# Sheet1.net
KiCad netlist of a schematic drawn in Altium Designer
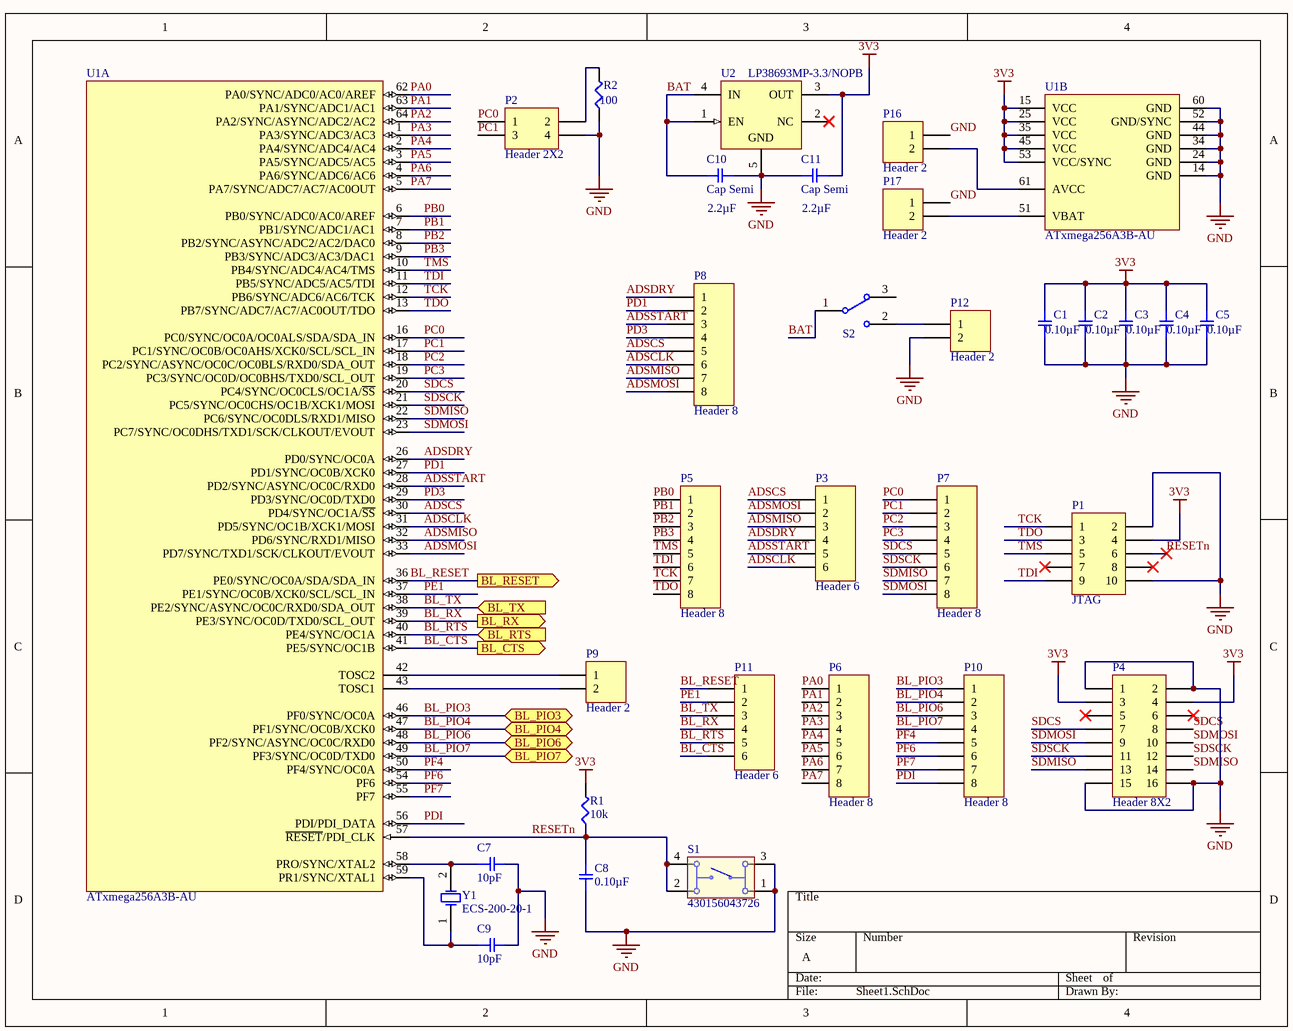
[diagram p0: Sheet1.SchDoc]

(export (version "E")
  (design (tool "Eeschema 10.0.6"))
  (components
    (comp (ref "C1")
      (value "0.10µF")
      (footprint "SMD-0805C")
      (description "CAP CER 0.1UF 50V X7R 0805")
      (fields
        (field (name "DIGI-KEY PART NUMBER") "490-11955-1-ND")
        (field (name "PART NUMBER") "GCD21BR71H104KA01L")
      )
      (libsource (lib "capacitor_murata_0805") (part "GCD21BR71H104KA01L"))
    )
    (comp (ref "C2")
      (value "0.10µF")
      (footprint "SMD-0805C")
      (description "CAP CER 0.1UF 50V X7R 0805")
      (fields
        (field (name "DIGI-KEY PART NUMBER") "490-11955-1-ND")
        (field (name "PART NUMBER") "GCD21BR71H104KA01L")
      )
      (libsource (lib "capacitor_murata_0805") (part "GCD21BR71H104KA01L"))
    )
    (comp (ref "C3")
      (value "0.10µF")
      (footprint "SMD-0805C")
      (description "CAP CER 0.1UF 50V X7R 0805")
      (fields
        (field (name "DIGI-KEY PART NUMBER") "490-11955-1-ND")
        (field (name "PART NUMBER") "GCD21BR71H104KA01L")
      )
      (libsource (lib "capacitor_murata_0805") (part "GCD21BR71H104KA01L"))
    )
    (comp (ref "C4")
      (value "0.10µF")
      (footprint "SMD-0805C")
      (description "CAP CER 0.1UF 50V X7R 0805")
      (fields
        (field (name "DIGI-KEY PART NUMBER") "490-11955-1-ND")
        (field (name "PART NUMBER") "GCD21BR71H104KA01L")
      )
      (libsource (lib "capacitor_murata_0805") (part "GCD21BR71H104KA01L"))
    )
    (comp (ref "C5")
      (value "0.10µF")
      (footprint "SMD-0805C")
      (description "CAP CER 0.1UF 50V X7R 0805")
      (fields
        (field (name "DIGI-KEY PART NUMBER") "490-11955-1-ND")
        (field (name "PART NUMBER") "GCD21BR71H104KA01L")
      )
      (libsource (lib "capacitor_murata_0805") (part "GCD21BR71H104KA01L"))
    )
    (comp (ref "C7")
      (value "10pF")
      (footprint "SMD-1206C")
      (description "CAP CER 10PF 630V U2J 1206")
      (fields
        (field (name "DIGI-KEY PART NUMBER") "490-6495-1-ND")
        (field (name "PART NUMBER") "GRM31A7U2J100JW31D")
      )
      (libsource (lib "capacitor_murata_1206") (part "GRM31A7U2J100JW31D"))
    )
    (comp (ref "C8")
      (value "0.10µF")
      (footprint "SMD-0805C")
      (description "CAP CER 0.1UF 50V X7R 0805")
      (fields
        (field (name "DIGI-KEY PART NUMBER") "490-11955-1-ND")
        (field (name "PART NUMBER") "GCD21BR71H104KA01L")
      )
      (libsource (lib "capacitor_murata_0805") (part "GCD21BR71H104KA01L"))
    )
    (comp (ref "C9")
      (value "10pF")
      (footprint "SMD-1206C")
      (description "CAP CER 10PF 630V U2J 1206")
      (fields
        (field (name "DIGI-KEY PART NUMBER") "490-6495-1-ND")
        (field (name "PART NUMBER") "GRM31A7U2J100JW31D")
      )
      (libsource (lib "capacitor_murata_1206") (part "GRM31A7U2J100JW31D"))
    )
    (comp (ref "C10")
      (value "Cap Semi")
      (footprint "C1206")
      (description "CAP CER 2.2UF 50V X7R 1206")
      (fields
        (field (name "ALTIUM_VALUE") "2.2µF")
        (field (name "DIGI-KEY PART NUMBER") "490-5809-1-ND")
        (field (name "PART NUMBER") "GCJ31CR71H225KA12L")
      )
      (libsource (lib "capacitor_murata_1206") (part "GCJ31CR71H225KA12L"))
    )
    (comp (ref "C11")
      (value "Cap Semi")
      (footprint "C1206")
      (description "CAP CER 2.2UF 50V X7R 1206")
      (fields
        (field (name "ALTIUM_VALUE") "2.2µF")
        (field (name "DIGI-KEY PART NUMBER") "490-5809-1-ND")
        (field (name "PART NUMBER") "GCJ31CR71H225KA12L")
      )
      (libsource (lib "capacitor_murata_1206") (part "GCJ31CR71H225KA12L"))
    )
    (comp (ref "P1")
      (value "JTAG")
      (footprint "HDR2X5")
      (description "Header, 5-Pin, Dual row")
      (fields (field (name "PUBLISHER") "Altium Limited"))
      (libsource (lib "Miscellaneous Connectors") (part "Header 5X2"))
    )
    (comp (ref "P2")
      (value "Header 2X2")
      (footprint "HDR2X2")
      (description "Header, 2-Pin, Dual row")
      (fields (field (name "PUBLISHER") "Altium Limited"))
      (libsource (lib "Miscellaneous Connectors") (part "Header 2X2"))
    )
    (comp (ref "P3")
      (value "Header 6")
      (footprint "HDR1X6")
      (description "Header, 6-Pin")
      (fields (field (name "PUBLISHER") "Altium Limited"))
      (libsource (lib "Miscellaneous Connectors") (part "Header 6"))
    )
    (comp (ref "P4")
      (value "Header 8X2")
      (footprint "HDR2X8")
      (description "Header, 8-Pin, Dual row")
      (fields (field (name "PUBLISHER") "Altium Limited"))
      (libsource (lib "Miscellaneous Connectors") (part "Header 8X2"))
    )
    (comp (ref "P5")
      (value "Header 8")
      (footprint "HDR1X8")
      (description "Header, 8-Pin")
      (fields (field (name "PUBLISHER") "Altium Limited"))
      (libsource (lib "Miscellaneous Connectors") (part "Header 8"))
    )
    (comp (ref "P6")
      (value "Header 8")
      (footprint "HDR1X8")
      (description "Header, 8-Pin")
      (fields (field (name "PUBLISHER") "Altium Limited"))
      (libsource (lib "Miscellaneous Connectors") (part "Header 8"))
    )
    (comp (ref "P7")
      (value "Header 8")
      (footprint "HDR1X8")
      (description "Header, 8-Pin")
      (fields (field (name "PUBLISHER") "Altium Limited"))
      (libsource (lib "Miscellaneous Connectors") (part "Header 8"))
    )
    (comp (ref "P8")
      (value "Header 8")
      (footprint "HDR1X8")
      (description "Header, 8-Pin")
      (fields (field (name "PUBLISHER") "Altium Limited"))
      (libsource (lib "Miscellaneous Connectors") (part "Header 8"))
    )
    (comp (ref "P9")
      (value "Header 2")
      (footprint "HDR1X2")
      (description "Header, 2-Pin")
      (fields (field (name "PUBLISHER") "Altium Limited"))
      (libsource (lib "Miscellaneous Connectors") (part "Header 2"))
    )
    (comp (ref "P10")
      (value "Header 8")
      (footprint "HDR1X8")
      (description "Header, 8-Pin")
      (fields (field (name "PUBLISHER") "Altium Limited"))
      (libsource (lib "Miscellaneous Connectors") (part "Header 8"))
    )
    (comp (ref "P11")
      (value "Header 6")
      (footprint "HDR1X6")
      (description "Header, 6-Pin")
      (fields (field (name "PUBLISHER") "Altium Limited"))
      (libsource (lib "Miscellaneous Connectors") (part "Header 6"))
    )
    (comp (ref "P12")
      (value "Header 2")
      (footprint "HDR1X2")
      (description "Header, 2-Pin")
      (fields (field (name "PUBLISHER") "Altium Limited"))
      (libsource (lib "Miscellaneous Connectors") (part "Header 2"))
    )
    (comp (ref "P16")
      (value "Header 2")
      (footprint "HDR1X2")
      (description "Header, 2-Pin")
      (fields (field (name "PUBLISHER") "Altium Limited"))
      (libsource (lib "") (part "Header 2_1"))
    )
    (comp (ref "P17")
      (value "Header 2")
      (footprint "HDR1X2")
      (description "Header, 2-Pin")
      (fields (field (name "PUBLISHER") "Altium Limited"))
      (libsource (lib "") (part "Header 2_1"))
    )
    (comp (ref "R1")
      (value "10k")
      (footprint "SMD-1206-RES")
      (description "RES SMD 10K OHM 1% 1/4W 1206")
      (fields
        (field (name "PART NUMBER") "ERJ-8ENF1002V")
        (field (name "DIGI-KEY PART NUMBER") "P10.0KFCT-ND")
      )
      (libsource (lib "Panasonic_ERJ_1206") (part "ERJ-8ENF1002V"))
    )
    (comp (ref "R2")
      (value "100")
      (footprint "SMD-0805-RES")
      (description "RES SMD 100 OHM 1% 1/8W 0805")
      (fields (field (name "PART NUMBER") "ERJ-6ENF1000V") (field (name "DIGI-KEY PART NUMBER") "P100CCT-ND"))
      (libsource (lib "Panasonic_ERJ_0805") (part "ERJ-6ENF1000V"))
    )
    (comp (ref "S1")
      (value "430156043726")
      (footprint "430156043726")
      (description "WS-TATV THT Tact Switch 6X6 mm")
      (libsource (lib "WS-TATV THT Tact Switch 6X6 mm") (part "430156043726"))
    )
    (comp (ref "S2")
      (value "450301014042")
      (footprint "450301014042")
      (description "10x2.5mm THT WS-SLTV")
      (fields (field (name "PUBLISHER") "Wurth Elektronik"))
      (libsource (lib "Altium_WS-SLTV (rev17b)edited2") (part "450301014042"))
    )
    (comp (ref "U1")
      (value "ATxmega256A3B-AU")
      (footprint "64A_N")
      (libsource (lib "Atmel Microcontroller AVR XMEGA") (part "ATxmega256A3B-AU"))
    )
    (comp (ref "U2")
      (value "LP38693MP-3.3/NOPB")
      (footprint "MP05A_N")
      (fields (field (name "MANUFACTURER") "National Semiconductor"))
      (libsource (lib "National Semiconductor LDO") (part "LP38693MP-3.3/NOPB"))
    )
    (comp (ref "Y1")
      (value "ECS-200-20-1")
      (footprint "HC-49U")
      (description "Crystal Oscillator")
      (fields (field (name "PUBLISHER") "Altium Limited"))
      (libsource (lib "ECS Crystal Oscillator") (part "ECS-200-20-1"))
    )
  )
  (nets
    (net (code "1") (name "/ADSCLK") (class "Default")
      (node (ref "P3") (pin "6") (pinfunction "6_6") (pintype "passive"))
      (node (ref "P8") (pin "6") (pinfunction "6_6") (pintype "passive"))
      (node (ref "U1") (pin "31") (pinfunction "PD5/SYNC/OC1B/XCK1/MOSI_31") (pintype "bidirectional"))
    )
    (net (code "2") (name "/ADSCS") (class "Default")
      (node (ref "P3") (pin "1") (pinfunction "1_1") (pintype "passive"))
      (node (ref "P8") (pin "5") (pinfunction "5_5") (pintype "passive"))
      (node (ref "U1") (pin "30") (pinfunction "PD4/SYNC/OC1A/~{SS}_30") (pintype "bidirectional"))
    )
    (net (code "3") (name "/ADSDRY") (class "Default")
      (node (ref "P3") (pin "4") (pinfunction "4_4") (pintype "passive"))
      (node (ref "P8") (pin "1") (pinfunction "1_1") (pintype "passive"))
      (node (ref "U1") (pin "26") (pinfunction "PD0/SYNC/OC0A_26") (pintype "bidirectional"))
    )
    (net (code "4") (name "/ADSMISO") (class "Default")
      (node (ref "P3") (pin "3") (pinfunction "3_3") (pintype "passive"))
      (node (ref "P8") (pin "7") (pinfunction "7_7") (pintype "passive"))
      (node (ref "U1") (pin "32") (pinfunction "PD6/SYNC/RXD1/MISO_32") (pintype "bidirectional"))
    )
    (net (code "5") (name "/ADSMOSI") (class "Default")
      (node (ref "P3") (pin "2") (pinfunction "2_2") (pintype "passive"))
      (node (ref "P8") (pin "8") (pinfunction "8_8") (pintype "passive"))
      (node (ref "U1") (pin "33") (pinfunction "PD7/SYNC/TXD1/SCK/CLKOUT/EVOUT_33") (pintype "bidirectional"))
    )
    (net (code "6") (name "/ADSSTART") (class "Default")
      (node (ref "P3") (pin "5") (pinfunction "5_5") (pintype "passive"))
      (node (ref "P8") (pin "3") (pinfunction "3_3") (pintype "passive"))
      (node (ref "U1") (pin "28") (pinfunction "PD2/SYNC/ASYNC/OC0C/RXD0_28") (pintype "bidirectional"))
    )
    (net (code "7") (name "/BAT") (class "Default")
      (node (ref "C10") (pin "2") (pinfunction "2_2") (pintype "passive"))
      (node (ref "S2") (pin "1") (pinfunction "COM_1") (pintype "passive"))
      (node (ref "U2") (pin "1") (pinfunction "EN_1") (pintype "input"))
      (node (ref "U2") (pin "4") (pinfunction "IN_4") (pintype "power_in"))
    )
    (net (code "8") (name "/BL_CTS") (class "Default")
      (node (ref "P11") (pin "6") (pinfunction "6_6") (pintype "passive"))
      (node (ref "U1") (pin "41") (pinfunction "PE5/SYNC/OC1B_41") (pintype "bidirectional"))
    )
    (net (code "9") (name "/BL_PIO3") (class "Default")
      (node (ref "P10") (pin "1") (pinfunction "1_1") (pintype "passive"))
      (node (ref "U1") (pin "46") (pinfunction "PF0/SYNC/OC0A_46") (pintype "bidirectional"))
    )
    (net (code "10") (name "/BL_PIO4") (class "Default")
      (node (ref "P10") (pin "2") (pinfunction "2_2") (pintype "passive"))
      (node (ref "U1") (pin "47") (pinfunction "PF1/SYNC/OC0B/XCK0_47") (pintype "bidirectional"))
    )
    (net (code "11") (name "/BL_PIO6") (class "Default")
      (node (ref "P10") (pin "3") (pinfunction "3_3") (pintype "passive"))
      (node (ref "U1") (pin "48") (pinfunction "PF2/SYNC/ASYNC/OC0C/RXD0_48") (pintype "bidirectional"))
    )
    (net (code "12") (name "/BL_PIO7") (class "Default")
      (node (ref "P10") (pin "4") (pinfunction "4_4") (pintype "passive"))
      (node (ref "U1") (pin "49") (pinfunction "PF3/SYNC/OC0D/TXD0_49") (pintype "bidirectional"))
    )
    (net (code "13") (name "/BL_RESET") (class "Default")
      (node (ref "P11") (pin "1") (pinfunction "1_1") (pintype "passive"))
      (node (ref "U1") (pin "36") (pinfunction "PE0/SYNC/OC0A/SDA/SDA_IN_36") (pintype "bidirectional"))
    )
    (net (code "14") (name "/BL_RTS") (class "Default")
      (node (ref "P11") (pin "5") (pinfunction "5_5") (pintype "passive"))
      (node (ref "U1") (pin "40") (pinfunction "PE4/SYNC/OC1A_40") (pintype "bidirectional"))
    )
    (net (code "15") (name "/BL_RX") (class "Default")
      (node (ref "P11") (pin "4") (pinfunction "4_4") (pintype "passive"))
      (node (ref "U1") (pin "39") (pinfunction "PE3/SYNC/OC0D/TXD0/SCL_OUT_39") (pintype "bidirectional"))
    )
    (net (code "16") (name "/BL_TX") (class "Default")
      (node (ref "P11") (pin "3") (pinfunction "3_3") (pintype "passive"))
      (node (ref "U1") (pin "38") (pinfunction "PE2/SYNC/ASYNC/OC0C/RXD0/SDA_OUT_38") (pintype "bidirectional"))
    )
    (net (code "17") (name "/PA0") (class "Default")
      (node (ref "P6") (pin "1") (pinfunction "1_1") (pintype "passive"))
      (node (ref "U1") (pin "62") (pinfunction "PA0/SYNC/ADC0/AC0/AREF_62") (pintype "bidirectional"))
    )
    (net (code "18") (name "/PA1") (class "Default")
      (node (ref "P6") (pin "2") (pinfunction "2_2") (pintype "passive"))
      (node (ref "U1") (pin "63") (pinfunction "PA1/SYNC/ADC1/AC1_63") (pintype "bidirectional"))
    )
    (net (code "19") (name "/PA2") (class "Default")
      (node (ref "P6") (pin "3") (pinfunction "3_3") (pintype "passive"))
      (node (ref "U1") (pin "64") (pinfunction "PA2/SYNC/ASYNC/ADC2/AC2_64") (pintype "bidirectional"))
    )
    (net (code "20") (name "/PA3") (class "Default")
      (node (ref "P6") (pin "4") (pinfunction "4_4") (pintype "passive"))
      (node (ref "U1") (pin "1") (pinfunction "PA3/SYNC/ADC3/AC3_1") (pintype "bidirectional"))
    )
    (net (code "21") (name "/PA4") (class "Default")
      (node (ref "P6") (pin "5") (pinfunction "5_5") (pintype "passive"))
      (node (ref "U1") (pin "2") (pinfunction "PA4/SYNC/ADC4/AC4_2") (pintype "bidirectional"))
    )
    (net (code "22") (name "/PA5") (class "Default")
      (node (ref "P6") (pin "6") (pinfunction "6_6") (pintype "passive"))
      (node (ref "U1") (pin "3") (pinfunction "PA5/SYNC/ADC5/AC5_3") (pintype "bidirectional"))
    )
    (net (code "23") (name "/PA6") (class "Default")
      (node (ref "P6") (pin "7") (pinfunction "7_7") (pintype "passive"))
      (node (ref "U1") (pin "4") (pinfunction "PA6/SYNC/ADC6/AC6_4") (pintype "bidirectional"))
    )
    (net (code "24") (name "/PA7") (class "Default")
      (node (ref "P6") (pin "8") (pinfunction "8_8") (pintype "passive"))
      (node (ref "U1") (pin "5") (pinfunction "PA7/SYNC/ADC7/AC7/AC0OUT_5") (pintype "bidirectional"))
    )
    (net (code "25") (name "/PB0") (class "Default")
      (node (ref "P5") (pin "1") (pinfunction "1_1") (pintype "passive"))
      (node (ref "U1") (pin "6") (pinfunction "PB0/SYNC/ADC0/AC0/AREF_6") (pintype "bidirectional"))
    )
    (net (code "26") (name "/PB1") (class "Default")
      (node (ref "P5") (pin "2") (pinfunction "2_2") (pintype "passive"))
      (node (ref "U1") (pin "7") (pinfunction "PB1/SYNC/ADC1/AC1_7") (pintype "bidirectional"))
    )
    (net (code "27") (name "/PB2") (class "Default")
      (node (ref "P5") (pin "3") (pinfunction "3_3") (pintype "passive"))
      (node (ref "U1") (pin "8") (pinfunction "PB2/SYNC/ASYNC/ADC2/AC2/DAC0_8") (pintype "bidirectional"))
    )
    (net (code "28") (name "/PB3") (class "Default")
      (node (ref "P5") (pin "4") (pinfunction "4_4") (pintype "passive"))
      (node (ref "U1") (pin "9") (pinfunction "PB3/SYNC/ADC3/AC3/DAC1_9") (pintype "bidirectional"))
    )
    (net (code "29") (name "/PC0") (class "Default")
      (node (ref "P2") (pin "1") (pinfunction "1_1") (pintype "passive"))
      (node (ref "P7") (pin "1") (pinfunction "1_1") (pintype "passive"))
      (node (ref "U1") (pin "16") (pinfunction "PC0/SYNC/OC0A/OC0ALS/SDA/SDA_IN_16") (pintype "bidirectional"))
    )
    (net (code "30") (name "/PC1") (class "Default")
      (node (ref "P2") (pin "3") (pinfunction "3_3") (pintype "passive"))
      (node (ref "P7") (pin "2") (pinfunction "2_2") (pintype "passive"))
      (node (ref "U1") (pin "17") (pinfunction "PC1/SYNC/OC0B/OC0AHS/XCK0/SCL/SCL_IN_17") (pintype "bidirectional"))
    )
    (net (code "31") (name "/PC2") (class "Default")
      (node (ref "P7") (pin "3") (pinfunction "3_3") (pintype "passive"))
      (node (ref "U1") (pin "18") (pinfunction "PC2/SYNC/ASYNC/OC0C/OC0BLS/RXD0/SDA_OUT_18") (pintype "bidirectional"))
    )
    (net (code "32") (name "/PC3") (class "Default")
      (node (ref "P7") (pin "4") (pinfunction "4_4") (pintype "passive"))
      (node (ref "U1") (pin "19") (pinfunction "PC3/SYNC/OC0D/OC0BHS/TXD0/SCL_OUT_19") (pintype "bidirectional"))
    )
    (net (code "33") (name "/PD1") (class "Default")
      (node (ref "P8") (pin "2") (pinfunction "2_2") (pintype "passive"))
      (node (ref "U1") (pin "27") (pinfunction "PD1/SYNC/OC0B/XCK0_27") (pintype "bidirectional"))
    )
    (net (code "34") (name "/PD3") (class "Default")
      (node (ref "P8") (pin "4") (pinfunction "4_4") (pintype "passive"))
      (node (ref "U1") (pin "29") (pinfunction "PD3/SYNC/OC0D/TXD0_29") (pintype "bidirectional"))
    )
    (net (code "35") (name "/PDI") (class "Default")
      (node (ref "P10") (pin "8") (pinfunction "8_8") (pintype "passive"))
      (node (ref "U1") (pin "56") (pinfunction "PDI/PDI_DATA_56") (pintype "bidirectional"))
    )
    (net (code "36") (name "/PE1") (class "Default")
      (node (ref "P11") (pin "2") (pinfunction "2_2") (pintype "passive"))
      (node (ref "U1") (pin "37") (pinfunction "PE1/SYNC/OC0B/XCK0/SCL/SCL_IN_37") (pintype "bidirectional"))
    )
    (net (code "37") (name "/PF4") (class "Default")
      (node (ref "P10") (pin "5") (pinfunction "5_5") (pintype "passive"))
      (node (ref "U1") (pin "50") (pinfunction "PF4/SYNC/OC0A_50") (pintype "bidirectional"))
    )
    (net (code "38") (name "/PF6") (class "Default")
      (node (ref "P10") (pin "6") (pinfunction "6_6") (pintype "passive"))
      (node (ref "U1") (pin "54") (pinfunction "PF6_54") (pintype "bidirectional"))
    )
    (net (code "39") (name "/PF7") (class "Default")
      (node (ref "P10") (pin "7") (pinfunction "7_7") (pintype "passive"))
      (node (ref "U1") (pin "55") (pinfunction "PF7_55") (pintype "bidirectional"))
    )
    (net (code "40") (name "/RESETn") (class "Default")
      (node (ref "C8") (pin "2") (pinfunction "2_2") (pintype "passive"))
      (node (ref "P1") (pin "6") (pinfunction "6_6") (pintype "passive"))
      (node (ref "R1") (pin "1") (pinfunction "1_1") (pintype "passive"))
      (node (ref "S1") (pin "2") (pinfunction "2_2") (pintype "passive"))
      (node (ref "S1") (pin "4") (pinfunction "4_4") (pintype "passive"))
      (node (ref "U1") (pin "57") (pinfunction "~{RESET}/PDI_CLK_57") (pintype "input"))
    )
    (net (code "41") (name "/SDCS") (class "Default")
      (node (ref "P4") (pin "7") (pinfunction "7_7") (pintype "passive"))
      (node (ref "P4") (pin "8") (pinfunction "8_8") (pintype "passive"))
      (node (ref "P7") (pin "5") (pinfunction "5_5") (pintype "passive"))
      (node (ref "U1") (pin "20") (pinfunction "PC4/SYNC/OC0CLS/OC1A/~{SS}_20") (pintype "bidirectional"))
    )
    (net (code "42") (name "/SDMISO") (class "Default")
      (node (ref "P4") (pin "13") (pinfunction "13_13") (pintype "passive"))
      (node (ref "P4") (pin "14") (pinfunction "14_14") (pintype "passive"))
      (node (ref "P7") (pin "7") (pinfunction "7_7") (pintype "passive"))
      (node (ref "U1") (pin "22") (pinfunction "PC6/SYNC/OC0DLS/RXD1/MISO_22") (pintype "bidirectional"))
    )
    (net (code "43") (name "/SDMOSI") (class "Default")
      (node (ref "P4") (pin "10") (pinfunction "10_10") (pintype "passive"))
      (node (ref "P4") (pin "9") (pinfunction "9_9") (pintype "passive"))
      (node (ref "P7") (pin "8") (pinfunction "8_8") (pintype "passive"))
      (node (ref "U1") (pin "23") (pinfunction "PC7/SYNC/OC0DHS/TXD1/SCK/CLKOUT/EVOUT_23") (pintype "bidirectional"))
    )
    (net (code "44") (name "/SDSCK") (class "Default")
      (node (ref "P4") (pin "11") (pinfunction "11_11") (pintype "passive"))
      (node (ref "P4") (pin "12") (pinfunction "12_12") (pintype "passive"))
      (node (ref "P7") (pin "6") (pinfunction "6_6") (pintype "passive"))
      (node (ref "U1") (pin "21") (pinfunction "PC5/SYNC/OC0CHS/OC1B/XCK1/MOSI_21") (pintype "bidirectional"))
    )
    (net (code "45") (name "/TCK") (class "Default")
      (node (ref "P1") (pin "1") (pinfunction "1_1") (pintype "passive"))
      (node (ref "P5") (pin "7") (pinfunction "7_7") (pintype "passive"))
      (node (ref "U1") (pin "12") (pinfunction "PB6/SYNC/ADC6/AC6/TCK_12") (pintype "bidirectional"))
    )
    (net (code "46") (name "/TDI") (class "Default")
      (node (ref "P1") (pin "9") (pinfunction "9_9") (pintype "passive"))
      (node (ref "P5") (pin "6") (pinfunction "6_6") (pintype "passive"))
      (node (ref "U1") (pin "11") (pinfunction "PB5/SYNC/ADC5/AC5/TDI_11") (pintype "bidirectional"))
    )
    (net (code "47") (name "/TDO") (class "Default")
      (node (ref "P1") (pin "3") (pinfunction "3_3") (pintype "passive"))
      (node (ref "P5") (pin "8") (pinfunction "8_8") (pintype "passive"))
      (node (ref "U1") (pin "13") (pinfunction "PB7/SYNC/ADC7/AC7/AC0OUT/TDO_13") (pintype "bidirectional"))
    )
    (net (code "48") (name "/TMS") (class "Default")
      (node (ref "P1") (pin "5") (pinfunction "5_5") (pintype "passive"))
      (node (ref "P5") (pin "5") (pinfunction "5_5") (pintype "passive"))
      (node (ref "U1") (pin "10") (pinfunction "PB4/SYNC/ADC4/AC4/TMS_10") (pintype "bidirectional"))
    )
    (net (code "49") (name "3V3") (class "Default")
      (node (ref "C1") (pin "2") (pinfunction "2_2") (pintype "passive"))
      (node (ref "C11") (pin "1") (pinfunction "1_1") (pintype "passive"))
      (node (ref "C2") (pin "2") (pinfunction "2_2") (pintype "passive"))
      (node (ref "C3") (pin "2") (pinfunction "2_2") (pintype "passive"))
      (node (ref "C4") (pin "2") (pinfunction "2_2") (pintype "passive"))
      (node (ref "C5") (pin "2") (pinfunction "2_2") (pintype "passive"))
      (node (ref "P1") (pin "4") (pinfunction "4_4") (pintype "passive"))
      (node (ref "P4") (pin "3") (pinfunction "3_3") (pintype "passive"))
      (node (ref "P4") (pin "4") (pinfunction "4_4") (pintype "passive"))
      (node (ref "R1") (pin "2") (pinfunction "2_2") (pintype "passive"))
      (node (ref "U1") (pin "15") (pinfunction "VCC_15") (pintype "power_in"))
      (node (ref "U1") (pin "25") (pinfunction "VCC_25") (pintype "power_in"))
      (node (ref "U1") (pin "35") (pinfunction "VCC_35") (pintype "power_in"))
      (node (ref "U1") (pin "45") (pinfunction "VCC_45") (pintype "power_in"))
      (node (ref "U1") (pin "53") (pinfunction "VCC/SYNC_53") (pintype "power_in"))
      (node (ref "U2") (pin "3") (pinfunction "OUT_3") (pintype "power_in"))
    )
    (net (code "50") (name "GND") (class "Default")
      (node (ref "C1") (pin "1") (pinfunction "1_1") (pintype "passive"))
      (node (ref "C10") (pin "1") (pinfunction "1_1") (pintype "passive"))
      (node (ref "C11") (pin "2") (pinfunction "2_2") (pintype "passive"))
      (node (ref "C2") (pin "1") (pinfunction "1_1") (pintype "passive"))
      (node (ref "C3") (pin "1") (pinfunction "1_1") (pintype "passive"))
      (node (ref "C4") (pin "1") (pinfunction "1_1") (pintype "passive"))
      (node (ref "C5") (pin "1") (pinfunction "1_1") (pintype "passive"))
      (node (ref "C7") (pin "2") (pinfunction "2_2") (pintype "passive"))
      (node (ref "C8") (pin "1") (pinfunction "1_1") (pintype "passive"))
      (node (ref "C9") (pin "2") (pinfunction "2_2") (pintype "passive"))
      (node (ref "P1") (pin "10") (pinfunction "10_10") (pintype "passive"))
      (node (ref "P1") (pin "2") (pinfunction "2_2") (pintype "passive"))
      (node (ref "P12") (pin "2") (pinfunction "2_2") (pintype "passive"))
      (node (ref "P16") (pin "1") (pinfunction "1_1") (pintype "passive"))
      (node (ref "P17") (pin "1") (pinfunction "1_1") (pintype "passive"))
      (node (ref "P2") (pin "4") (pinfunction "4_4") (pintype "passive"))
      (node (ref "P4") (pin "1") (pinfunction "1_1") (pintype "passive"))
      (node (ref "P4") (pin "15") (pinfunction "15_15") (pintype "passive"))
      (node (ref "P4") (pin "16") (pinfunction "16_16") (pintype "passive"))
      (node (ref "P4") (pin "2") (pinfunction "2_2") (pintype "passive"))
      (node (ref "R2") (pin "1") (pinfunction "1_1") (pintype "passive"))
      (node (ref "S1") (pin "1") (pinfunction "1_1") (pintype "passive"))
      (node (ref "S1") (pin "3") (pinfunction "3_3") (pintype "passive"))
      (node (ref "U1") (pin "14") (pinfunction "GND_14") (pintype "power_in"))
      (node (ref "U1") (pin "24") (pinfunction "GND_24") (pintype "power_in"))
      (node (ref "U1") (pin "34") (pinfunction "GND_34") (pintype "power_in"))
      (node (ref "U1") (pin "44") (pinfunction "GND_44") (pintype "power_in"))
      (node (ref "U1") (pin "52") (pinfunction "GND/SYNC_52") (pintype "power_in"))
      (node (ref "U1") (pin "60") (pinfunction "GND_60") (pintype "power_in"))
      (node (ref "U2") (pin "5") (pinfunction "GND_5") (pintype "power_in"))
    )
    (net (code "51") (name "Net-(P2-Pad2)") (class "Default")
      (node (ref "P2") (pin "2") (pinfunction "2_2") (pintype "passive"))
      (node (ref "R2") (pin "2") (pinfunction "2_2") (pintype "passive"))
    )
    (net (code "52") (name "Net-(P12-Pad1)") (class "Default")
      (node (ref "P12") (pin "1") (pinfunction "1_1") (pintype "passive"))
      (node (ref "S2") (pin "2") (pinfunction "2_2") (pintype "passive"))
    )
    (net (code "53") (name "Net-(U1A-PR1{slash}SYNC{slash}XTAL1)") (class "Default")
      (node (ref "C9") (pin "1") (pinfunction "1_1") (pintype "passive"))
      (node (ref "U1") (pin "59") (pinfunction "PR1/SYNC/XTAL1_59") (pintype "bidirectional"))
      (node (ref "Y1") (pin "1") (pinfunction "OSC1_1") (pintype "passive"))
    )
    (net (code "54") (name "Net-(U1A-PRO{slash}SYNC{slash}XTAL2)") (class "Default")
      (node (ref "C7") (pin "1") (pinfunction "1_1") (pintype "passive"))
      (node (ref "U1") (pin "58") (pinfunction "PRO/SYNC/XTAL2_58") (pintype "bidirectional"))
      (node (ref "Y1") (pin "2") (pinfunction "OSC2_2") (pintype "passive"))
    )
    (net (code "55") (name "Net-(U1A-TOSC1)") (class "Default")
      (node (ref "P9") (pin "2") (pinfunction "2_2") (pintype "passive"))
      (node (ref "U1") (pin "43") (pinfunction "TOSC1_43") (pintype "passive"))
    )
    (net (code "56") (name "Net-(U1A-TOSC2)") (class "Default")
      (node (ref "P9") (pin "1") (pinfunction "1_1") (pintype "passive"))
      (node (ref "U1") (pin "42") (pinfunction "TOSC2_42") (pintype "passive"))
    )
    (net (code "57") (name "Net-(U1B-AVCC)") (class "Default")
      (node (ref "P16") (pin "2") (pinfunction "2_2") (pintype "passive"))
      (node (ref "U1") (pin "61") (pinfunction "AVCC_61") (pintype "power_in"))
    )
    (net (code "58") (name "Net-(U1B-VBAT)") (class "Default")
      (node (ref "P17") (pin "2") (pinfunction "2_2") (pintype "passive"))
      (node (ref "U1") (pin "51") (pinfunction "VBAT_51") (pintype "power_in"))
    )
    (net (code "59") (name "unconnected-(P1-Pad7)") (class "Default")
      (node (ref "P1") (pin "7") (pinfunction "7_7") (pintype "passive+no_connect"))
    )
    (net (code "60") (name "unconnected-(P1-Pad8)") (class "Default")
      (node (ref "P1") (pin "8") (pinfunction "8_8") (pintype "passive+no_connect"))
    )
    (net (code "61") (name "unconnected-(P4-Pad5)") (class "Default")
      (node (ref "P4") (pin "5") (pinfunction "5_5") (pintype "passive+no_connect"))
    )
    (net (code "62") (name "unconnected-(P4-Pad6)") (class "Default")
      (node (ref "P4") (pin "6") (pinfunction "6_6") (pintype "passive+no_connect"))
    )
    (net (code "63") (name "unconnected-(S2-Pad3)") (class "Default")
      (node (ref "S2") (pin "3") (pinfunction "3_3") (pintype "passive"))
    )
    (net (code "64") (name "unconnected-(U2-NC-Pad2)") (class "Default")
      (node (ref "U2") (pin "2") (pinfunction "NC_2") (pintype "passive+no_connect"))
    )
  )
)
